# MDBU004A_DRV888x_MSP430F2617.net
KiCad netlist of a schematic drawn in Altium Designer
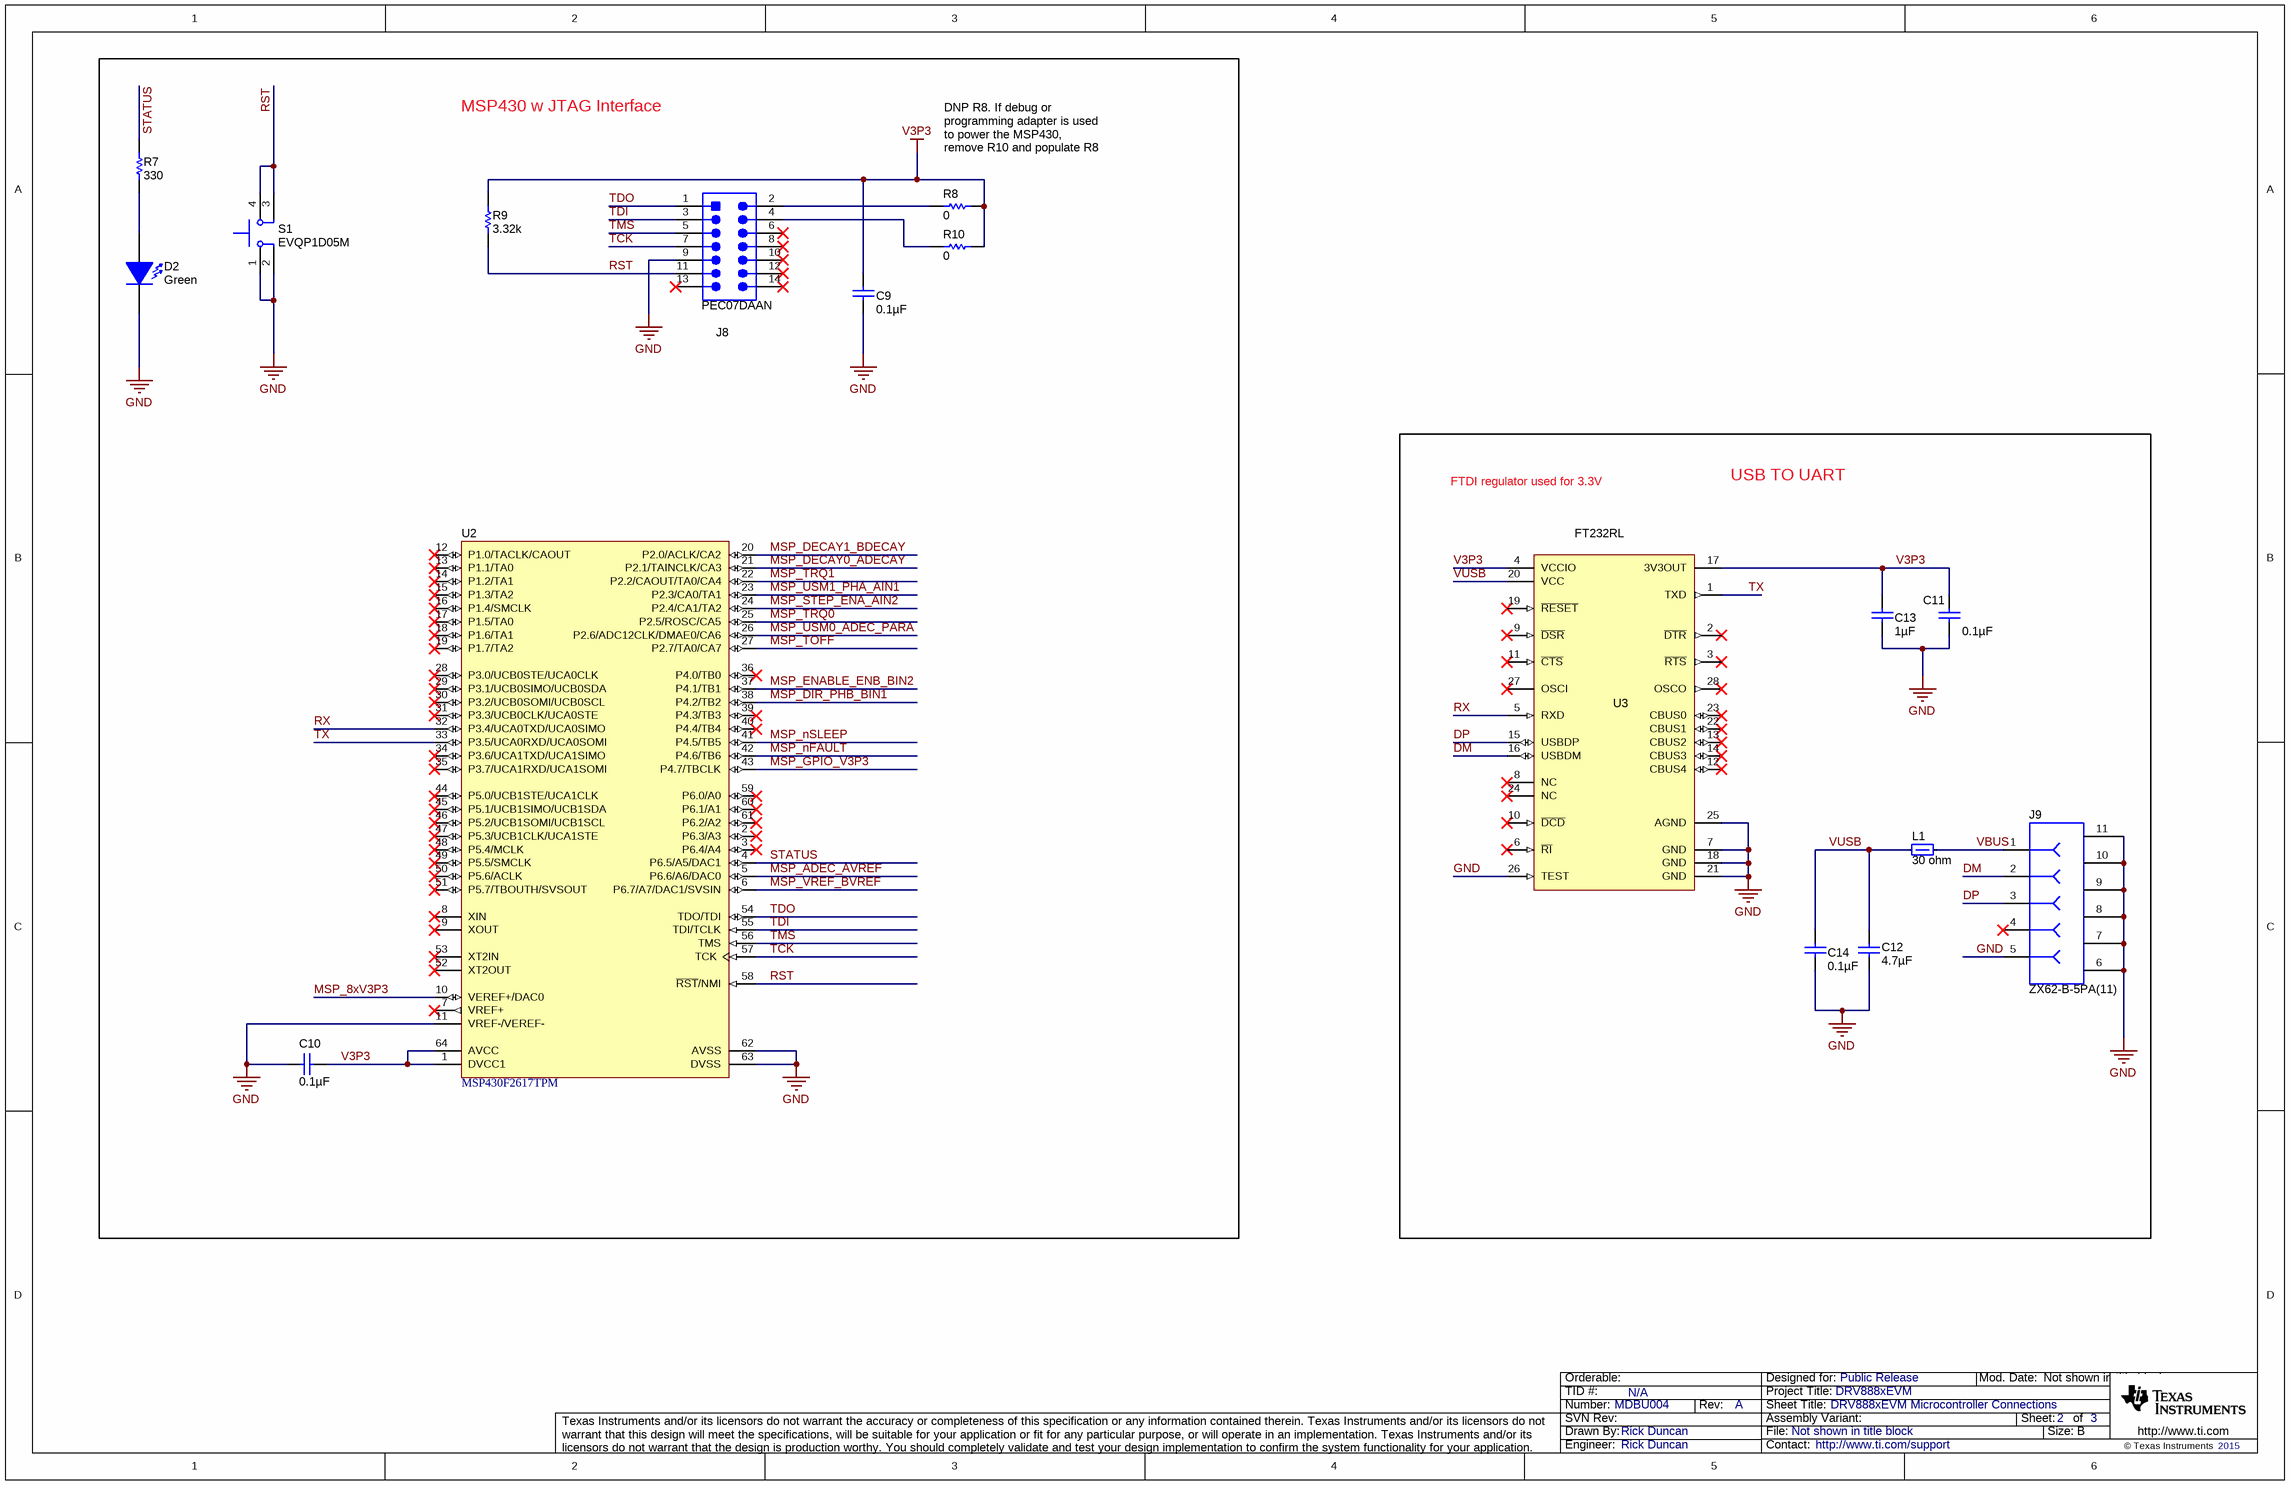
[diagram p0: MDBU004A_DRV888x_MSP430F2617.SchDoc]

(export (version "E")
  (design (tool "Eeschema 10.0.6"))
  (components
    (comp (ref "C9")
      (value "GRM155R61A104KA01D")
      (footprint "0402L")
      (description "CAP, CERM, 0.1 µF, 10 V, +/- 10%, X5R, 0402")
      (fields
        (field (name "MANUFACTURER") "MuRata")
        (field (name "VALUEDISPLAYED") "0.1µF")
        (field (name "PUBLISHER") "Texas Instruments")
      )
      (libsource (lib "Capacitor_Ceramic") (part "GRM155R61A104KA01D"))
    )
    (comp (ref "C10")
      (value "GRM155R61A104KA01D")
      (footprint "0402L")
      (description "CAP, CERM, 0.1 µF, 10 V, +/- 10%, X5R, 0402")
      (fields
        (field (name "MANUFACTURER") "MuRata")
        (field (name "VALUEDISPLAYED") "0.1µF")
        (field (name "PUBLISHER") "Texas Instruments")
      )
      (libsource (lib "Capacitor_Ceramic") (part "GRM155R61A104KA01D"))
    )
    (comp (ref "C11")
      (value "GRM155R61A104KA01D")
      (footprint "0402L")
      (description "CAP, CERM, 0.1 µF, 10 V, +/- 10%, X5R, 0402")
      (fields
        (field (name "MANUFACTURER") "MuRata")
        (field (name "VALUEDISPLAYED") "0.1µF")
        (field (name "PUBLISHER") "Texas Instruments")
      )
      (libsource (lib "Capacitor_Ceramic") (part "GRM155R61A104KA01D"))
    )
    (comp (ref "C12")
      (value "CGB3B1X5R1A475K055AC")
      (footprint "0603L")
      (description "CAP, CERM, 4.7 µF, 10 V, +/- 10%, X5R, 0603")
      (fields
        (field (name "VALUEDISPLAYED") "4.7µF")
        (field (name "MANUFACTURER") "TDK")
        (field (name "PUBLISHER") "Texas Instruments")
      )
      (libsource (lib "Capacitor_Ceramic") (part "CGB3B1X5R1A475K055AC"))
    )
    (comp (ref "C13")
      (value "GRM155R61A105KE15D")
      (footprint "0402L")
      (description "CAP, CERM, 1 µF, 10 V, +/- 10%, X5R, 0402")
      (fields
        (field (name "MANUFACTURER") "MuRata")
        (field (name "VALUEDISPLAYED") "1µF")
        (field (name "PUBLISHER") "Texas Instruments")
      )
      (libsource (lib "Capacitor_Ceramic") (part "GRM155R61A105KE15D"))
    )
    (comp (ref "C14")
      (value "GRM155R61A104KA01D")
      (footprint "0402L")
      (description "CAP, CERM, 0.1 µF, 10 V, +/- 10%, X5R, 0402")
      (fields
        (field (name "MANUFACTURER") "MuRata")
        (field (name "VALUEDISPLAYED") "0.1µF")
        (field (name "PUBLISHER") "Texas Instruments")
      )
      (libsource (lib "Capacitor_Ceramic") (part "GRM155R61A104KA01D"))
    )
    (comp (ref "D2")
      (value "Green")
      (footprint "LED_LTST-C190")
      (description "LED, Green, SMD")
      (fields
        (field (name "MANUFACTURER") "Lite-On")
        (field (name "PARTNUMBER") "LTST-C190GKT")
        (field (name "PUBLISHER") "Texas Instruments")
      )
      (libsource (lib "LED") (part "LTST-C190GKT"))
    )
    (comp (ref "J8")
      (value "PEC07DAAN")
      (footprint "CONN_PEC07DAAN")
      (description "Header, 100mil, 7x2, Tin, TH")
      (fields
        (field (name "MANUFACTURER") "Sullins Connector Solutions")
        (field (name "SYMBOLCREATOR") "a0412235")
        (field (name "PUBLISHER") "Texas Instruments")
      )
      (libsource (lib "Connectors_Sullins") (part "PEC07DAAN"))
    )
    (comp (ref "J9")
      (value "ZX62-B-5PA(11)")
      (footprint "CONN_USB_micro_ZX62-B-5PA")
      (description "Connector, Receptacle, Micro-USB Type B, R/A, Bottom Mount SMT")
      (fields
        (field (name "MANUFACTURER") "Hirose Electric Co. Ltd.")
        (field (name "SYMBOLCREATOR") "a0411947")
        (field (name "PUBLISHER") "Texas Instruments")
      )
      (libsource (lib "Connectors_Other") (part "ZX62-B-5PA(11)"))
    )
    (comp (ref "L1")
      (value "30 ohm")
      (footprint "0805L")
      (description "Ferrite Bead, 30 ohm @ 100 MHz, 1.5 A, 0805")
      (fields
        (field (name "MANUFACTURER") "TDK")
        (field (name "PARTNUMBER") "MMZ2012R300A")
        (field (name "PUBLISHER") "Texas Instruments")
      )
      (libsource (lib "FerriteBead") (part "MMZ2012R300A"))
    )
    (comp (ref "R7")
      (value "330")
      (footprint "0402L")
      (description "RES, 330, 5%, 0.063 W, 0402")
      (fields
        (field (name "MANUFACTURER") "Vishay-Dale")
        (field (name "PARTNUMBER") "CRCW0402330RJNED")
        (field (name "PUBLISHER") "Texas Instruments")
      )
      (libsource (lib "Resistor_0402") (part "CRCW0402330RJNED"))
    )
    (comp (ref "R8")
      (value "0")
      (footprint "0402L")
      (description "RES, 0, 5%, 0.063 W, 0402")
      (fields
        (field (name "MANUFACTURER") "Panasonic")
        (field (name "PARTNUMBER") "ERJ-2GE0R00X")
        (field (name "PUBLISHER") "Texas Instruments")
      )
      (libsource (lib "Resistor_0402") (part "ERJ-2GE0R00X"))
    )
    (comp (ref "R9")
      (value "3.32k")
      (footprint "0402L")
      (description "RES, 3.32 k, 1%, 0.063 W, 0402")
      (fields
        (field (name "MANUFACTURER") "Vishay-Dale")
        (field (name "PARTNUMBER") "CRCW04023K32FKED")
        (field (name "PUBLISHER") "Texas Instruments")
      )
      (libsource (lib "Resistor_0402") (part "CRCW04023K32FKED"))
    )
    (comp (ref "R10")
      (value "0")
      (footprint "0402L")
      (description "RES, 0, 5%, 0.063 W, 0402")
      (fields
        (field (name "MANUFACTURER") "Panasonic")
        (field (name "PARTNUMBER") "ERJ-2GE0R00X")
        (field (name "PUBLISHER") "Texas Instruments")
      )
      (libsource (lib "Resistor_0402") (part "ERJ-2GE0R00X"))
    )
    (comp (ref "S1")
      (value "EVQP1D05M")
      (footprint "SW_EVQxxx05M")
      (description "Switch, Tactile, SPST-NO, 0.05A, 12V, SMT")
      (fields
        (field (name "MANUFACTURER") "Panasonic")
        (field (name "SYMBOLCREATOR") "a0799628")
        (field (name "PUBLISHER") "Texas Instruments")
      )
      (libsource (lib "Switches") (part "EVQP1D05M"))
    )
    (comp (ref "U2")
      (value "MSP430F2617TPM")
      (footprint "PM0064A_L")
      (fields
        (field (name "MANUFACTURER") "Texas Instruments")
        (field (name "ALTERNATE PARTNUMBER") "Equivalent")
      )
      (libsource (lib "TI MCU MSP430") (part "MSP430F2617TPM"))
    )
    (comp (ref "U3")
      (value "FT232RL")
      (footprint "SSOP28_M")
      (description "USB to Serial UART, SSOP28")
      (fields
        (field (name "MANUFACTURER") "FTDI")
        (field (name "SYMBOLCREATOR") "x0208326")
        (field (name "PUBLISHER") "Texas Instruments")
      )
      (libsource (lib "Other_IC") (part "FT232RL"))
    )
  )
  (nets
    (net (code "1") (name "/DM") (class "Default")
      (node (ref "J9") (pin "2") (pinfunction "2_2") (pintype "passive"))
      (node (ref "U3") (pin "16") (pinfunction "USBDM_16") (pintype "bidirectional"))
    )
    (net (code "2") (name "/DP") (class "Default")
      (node (ref "J9") (pin "3") (pinfunction "3_3") (pintype "passive"))
      (node (ref "U3") (pin "15") (pinfunction "USBDP_15") (pintype "bidirectional"))
    )
    (net (code "3") (name "/MSP_8xV3P3") (class "Default")
      (node (ref "U2") (pin "10") (pinfunction "VEREF+/DAC0_10") (pintype "bidirectional"))
    )
    (net (code "4") (name "/MSP_ADEC_AVREF") (class "Default")
      (node (ref "U2") (pin "5") (pinfunction "P6.6/A6/DAC0_5") (pintype "bidirectional"))
    )
    (net (code "5") (name "/MSP_DECAY0_ADECAY") (class "Default")
      (node (ref "U2") (pin "21") (pinfunction "P2.1/TAINCLK/CA3_21") (pintype "bidirectional"))
    )
    (net (code "6") (name "/MSP_DECAY1_BDECAY") (class "Default")
      (node (ref "U2") (pin "20") (pinfunction "P2.0/ACLK/CA2_20") (pintype "bidirectional"))
    )
    (net (code "7") (name "/MSP_DIR_PHB_BIN1") (class "Default")
      (node (ref "U2") (pin "38") (pinfunction "P4.2/TB2_38") (pintype "bidirectional"))
    )
    (net (code "8") (name "/MSP_ENABLE_ENB_BIN2") (class "Default")
      (node (ref "U2") (pin "37") (pinfunction "P4.1/TB1_37") (pintype "bidirectional"))
    )
    (net (code "9") (name "/MSP_GPIO_V3P3") (class "Default")
      (node (ref "U2") (pin "43") (pinfunction "P4.7/TBCLK_43") (pintype "bidirectional"))
    )
    (net (code "10") (name "/MSP_STEP_ENA_AIN2") (class "Default")
      (node (ref "U2") (pin "24") (pinfunction "P2.4/CA1/TA2_24") (pintype "bidirectional"))
    )
    (net (code "11") (name "/MSP_TOFF") (class "Default")
      (node (ref "U2") (pin "27") (pinfunction "P2.7/TA0/CA7_27") (pintype "bidirectional"))
    )
    (net (code "12") (name "/MSP_TRQ0") (class "Default")
      (node (ref "U2") (pin "25") (pinfunction "P2.5/ROSC/CA5_25") (pintype "bidirectional"))
    )
    (net (code "13") (name "/MSP_TRQ1") (class "Default")
      (node (ref "U2") (pin "22") (pinfunction "P2.2/CAOUT/TA0/CA4_22") (pintype "bidirectional"))
    )
    (net (code "14") (name "/MSP_USM0_ADEC_PARA") (class "Default")
      (node (ref "U2") (pin "26") (pinfunction "P2.6/ADC12CLK/DMAE0/CA6_26") (pintype "bidirectional"))
    )
    (net (code "15") (name "/MSP_USM1_PHA_AIN1") (class "Default")
      (node (ref "U2") (pin "23") (pinfunction "P2.3/CA0/TA1_23") (pintype "bidirectional"))
    )
    (net (code "16") (name "/MSP_VREF_BVREF") (class "Default")
      (node (ref "U2") (pin "6") (pinfunction "P6.7/A7/DAC1/SVSIN_6") (pintype "bidirectional"))
    )
    (net (code "17") (name "/MSP_nFAULT") (class "Default")
      (node (ref "U2") (pin "42") (pinfunction "P4.6/TB6_42") (pintype "bidirectional"))
    )
    (net (code "18") (name "/MSP_nSLEEP") (class "Default")
      (node (ref "U2") (pin "41") (pinfunction "P4.5/TB5_41") (pintype "bidirectional"))
    )
    (net (code "19") (name "/RST") (class "Default")
      (node (ref "J8") (pin "11") (pinfunction "11_11") (pintype "passive"))
      (node (ref "R9") (pin "1") (pinfunction "1_1") (pintype "passive"))
      (node (ref "S1") (pin "3") (pinfunction "3_3") (pintype "passive"))
      (node (ref "S1") (pin "4") (pinfunction "4_4") (pintype "passive"))
      (node (ref "U2") (pin "58") (pinfunction "~{RST}/NMI_58") (pintype "input"))
    )
    (net (code "20") (name "/RX") (class "Default")
      (node (ref "U2") (pin "32") (pinfunction "P3.4/UCA0TXD/UCA0SIMO_32") (pintype "bidirectional"))
      (node (ref "U3") (pin "5") (pinfunction "RXD_5") (pintype "input"))
    )
    (net (code "21") (name "/STATUS") (class "Default")
      (node (ref "R7") (pin "2") (pinfunction "2_2") (pintype "passive"))
      (node (ref "U2") (pin "4") (pinfunction "P6.5/A5/DAC1_4") (pintype "bidirectional"))
    )
    (net (code "22") (name "/TCK") (class "Default")
      (node (ref "J8") (pin "7") (pinfunction "7_7") (pintype "passive"))
      (node (ref "U2") (pin "57") (pinfunction "TCK_57") (pintype "input"))
    )
    (net (code "23") (name "/TDI") (class "Default")
      (node (ref "J8") (pin "3") (pinfunction "3_3") (pintype "passive"))
      (node (ref "U2") (pin "55") (pinfunction "TDI/TCLK_55") (pintype "input"))
    )
    (net (code "24") (name "/TDO") (class "Default")
      (node (ref "J8") (pin "1") (pinfunction "1_1") (pintype "passive"))
      (node (ref "U2") (pin "54") (pinfunction "TDO/TDI_54") (pintype "bidirectional"))
    )
    (net (code "25") (name "/TMS") (class "Default")
      (node (ref "J8") (pin "5") (pinfunction "5_5") (pintype "passive"))
      (node (ref "U2") (pin "56") (pinfunction "TMS_56") (pintype "input"))
    )
    (net (code "26") (name "/TX") (class "Default")
      (node (ref "U2") (pin "33") (pinfunction "P3.5/UCA0RXD/UCA0SOMI_33") (pintype "bidirectional"))
      (node (ref "U3") (pin "1") (pinfunction "TXD_1") (pintype "output"))
    )
    (net (code "27") (name "/VBUS") (class "Default")
      (node (ref "J9") (pin "1") (pinfunction "1_1") (pintype "passive"))
      (node (ref "L1") (pin "2") (pinfunction "2_2") (pintype "passive"))
    )
    (net (code "28") (name "/VUSB") (class "Default")
      (node (ref "C12") (pin "1") (pinfunction "1_1") (pintype "passive"))
      (node (ref "C14") (pin "1") (pinfunction "1_1") (pintype "passive"))
      (node (ref "L1") (pin "1") (pinfunction "1_1") (pintype "passive"))
      (node (ref "U3") (pin "20") (pinfunction "VCC_20") (pintype "power_in"))
    )
    (net (code "29") (name "GND") (class "Default")
      (node (ref "C10") (pin "2") (pinfunction "2_2") (pintype "passive"))
      (node (ref "C11") (pin "2") (pinfunction "2_2") (pintype "passive"))
      (node (ref "C12") (pin "2") (pinfunction "2_2") (pintype "passive"))
      (node (ref "C13") (pin "2") (pinfunction "2_2") (pintype "passive"))
      (node (ref "C14") (pin "2") (pinfunction "2_2") (pintype "passive"))
      (node (ref "C9") (pin "2") (pinfunction "2_2") (pintype "passive"))
      (node (ref "D2") (pin "2") (pinfunction "K_2") (pintype "passive"))
      (node (ref "J8") (pin "9") (pinfunction "9_9") (pintype "passive"))
      (node (ref "J9") (pin "10") (pinfunction "10_10") (pintype "passive"))
      (node (ref "J9") (pin "11") (pinfunction "11_11") (pintype "passive"))
      (node (ref "J9") (pin "5") (pinfunction "5_5") (pintype "passive"))
      (node (ref "J9") (pin "6") (pinfunction "6_6") (pintype "passive"))
      (node (ref "J9") (pin "7") (pinfunction "7_7") (pintype "passive"))
      (node (ref "J9") (pin "8") (pinfunction "8_8") (pintype "passive"))
      (node (ref "J9") (pin "9") (pinfunction "9_9") (pintype "passive"))
      (node (ref "S1") (pin "1") (pinfunction "1_1") (pintype "passive"))
      (node (ref "S1") (pin "2") (pinfunction "2_2") (pintype "passive"))
      (node (ref "U2") (pin "11") (pinfunction "VREF-/VEREF-_11") (pintype "passive"))
      (node (ref "U2") (pin "62") (pinfunction "AVSS_62") (pintype "power_in"))
      (node (ref "U2") (pin "63") (pinfunction "DVSS_63") (pintype "power_in"))
      (node (ref "U3") (pin "18") (pinfunction "GND_18") (pintype "power_in"))
      (node (ref "U3") (pin "21") (pinfunction "GND_21") (pintype "power_in"))
      (node (ref "U3") (pin "25") (pinfunction "AGND_25") (pintype "power_in"))
      (node (ref "U3") (pin "26") (pinfunction "TEST_26") (pintype "input"))
      (node (ref "U3") (pin "7") (pinfunction "GND_7") (pintype "power_in"))
    )
    (net (code "30") (name "Net-(D2-A)") (class "Default")
      (node (ref "D2") (pin "1") (pinfunction "A_1") (pintype "passive"))
      (node (ref "R7") (pin "1") (pinfunction "1_1") (pintype "passive"))
    )
    (net (code "31") (name "Net-(J8-Pad2)") (class "Default")
      (node (ref "J8") (pin "2") (pinfunction "2_2") (pintype "passive"))
      (node (ref "R8") (pin "2") (pinfunction "2_2") (pintype "passive"))
    )
    (net (code "32") (name "Net-(J8-Pad4)") (class "Default")
      (node (ref "J8") (pin "4") (pinfunction "4_4") (pintype "passive"))
      (node (ref "R10") (pin "2") (pinfunction "2_2") (pintype "passive"))
    )
    (net (code "33") (name "V3P3") (class "Default")
      (node (ref "C10") (pin "1") (pinfunction "1_1") (pintype "passive"))
      (node (ref "C11") (pin "1") (pinfunction "1_1") (pintype "passive"))
      (node (ref "C13") (pin "1") (pinfunction "1_1") (pintype "passive"))
      (node (ref "C9") (pin "1") (pinfunction "1_1") (pintype "passive"))
      (node (ref "R10") (pin "1") (pinfunction "1_1") (pintype "passive"))
      (node (ref "R8") (pin "1") (pinfunction "1_1") (pintype "passive"))
      (node (ref "R9") (pin "2") (pinfunction "2_2") (pintype "passive"))
      (node (ref "U2") (pin "1") (pinfunction "DVCC1_1") (pintype "power_in"))
      (node (ref "U2") (pin "64") (pinfunction "AVCC_64") (pintype "power_in"))
      (node (ref "U3") (pin "17") (pinfunction "3V3OUT_17") (pintype "power_in"))
      (node (ref "U3") (pin "4") (pinfunction "VCCIO_4") (pintype "power_in"))
    )
    (net (code "34") (name "unconnected-(J8-Pad6)") (class "Default")
      (node (ref "J8") (pin "6") (pinfunction "6_6") (pintype "passive+no_connect"))
    )
    (net (code "35") (name "unconnected-(J8-Pad8)") (class "Default")
      (node (ref "J8") (pin "8") (pinfunction "8_8") (pintype "passive+no_connect"))
    )
    (net (code "36") (name "unconnected-(J8-Pad10)") (class "Default")
      (node (ref "J8") (pin "10") (pinfunction "10_10") (pintype "passive+no_connect"))
    )
    (net (code "37") (name "unconnected-(J8-Pad12)") (class "Default")
      (node (ref "J8") (pin "12") (pinfunction "12_12") (pintype "passive+no_connect"))
    )
    (net (code "38") (name "unconnected-(J8-Pad13)") (class "Default")
      (node (ref "J8") (pin "13") (pinfunction "13_13") (pintype "passive+no_connect"))
    )
    (net (code "39") (name "unconnected-(J8-Pad14)") (class "Default")
      (node (ref "J8") (pin "14") (pinfunction "14_14") (pintype "passive+no_connect"))
    )
    (net (code "40") (name "unconnected-(J9-Pad4)") (class "Default")
      (node (ref "J9") (pin "4") (pinfunction "4_4") (pintype "passive+no_connect"))
    )
    (net (code "41") (name "unconnected-(U2-P1.0{slash}TACLK{slash}CAOUT-Pad12)") (class "Default")
      (node (ref "U2") (pin "12") (pinfunction "P1.0/TACLK/CAOUT_12") (pintype "bidirectional+no_connect"))
    )
    (net (code "42") (name "unconnected-(U2-P1.1{slash}TA0-Pad13)") (class "Default")
      (node (ref "U2") (pin "13") (pinfunction "P1.1/TA0_13") (pintype "bidirectional+no_connect"))
    )
    (net (code "43") (name "unconnected-(U2-P1.2{slash}TA1-Pad14)") (class "Default")
      (node (ref "U2") (pin "14") (pinfunction "P1.2/TA1_14") (pintype "bidirectional+no_connect"))
    )
    (net (code "44") (name "unconnected-(U2-P1.3{slash}TA2-Pad15)") (class "Default")
      (node (ref "U2") (pin "15") (pinfunction "P1.3/TA2_15") (pintype "bidirectional+no_connect"))
    )
    (net (code "45") (name "unconnected-(U2-P1.4{slash}SMCLK-Pad16)") (class "Default")
      (node (ref "U2") (pin "16") (pinfunction "P1.4/SMCLK_16") (pintype "bidirectional+no_connect"))
    )
    (net (code "46") (name "unconnected-(U2-P1.5{slash}TA0-Pad17)") (class "Default")
      (node (ref "U2") (pin "17") (pinfunction "P1.5/TA0_17") (pintype "bidirectional+no_connect"))
    )
    (net (code "47") (name "unconnected-(U2-P1.6{slash}TA1-Pad18)") (class "Default")
      (node (ref "U2") (pin "18") (pinfunction "P1.6/TA1_18") (pintype "bidirectional+no_connect"))
    )
    (net (code "48") (name "unconnected-(U2-P1.7{slash}TA2-Pad19)") (class "Default")
      (node (ref "U2") (pin "19") (pinfunction "P1.7/TA2_19") (pintype "bidirectional+no_connect"))
    )
    (net (code "49") (name "unconnected-(U2-P3.0{slash}UCB0STE{slash}UCA0CLK-Pad28)") (class "Default")
      (node (ref "U2") (pin "28") (pinfunction "P3.0/UCB0STE/UCA0CLK_28") (pintype "bidirectional+no_connect"))
    )
    (net (code "50") (name "unconnected-(U2-P3.1{slash}UCB0SIMO{slash}UCB0SDA-Pad29)") (class "Default")
      (node (ref "U2") (pin "29") (pinfunction "P3.1/UCB0SIMO/UCB0SDA_29") (pintype "bidirectional+no_connect"))
    )
    (net (code "51") (name "unconnected-(U2-P3.2{slash}UCB0SOMI{slash}UCB0SCL-Pad30)") (class "Default")
      (node (ref "U2") (pin "30") (pinfunction "P3.2/UCB0SOMI/UCB0SCL_30") (pintype "bidirectional+no_connect"))
    )
    (net (code "52") (name "unconnected-(U2-P3.3{slash}UCB0CLK{slash}UCA0STE-Pad31)") (class "Default")
      (node (ref "U2") (pin "31") (pinfunction "P3.3/UCB0CLK/UCA0STE_31") (pintype "bidirectional+no_connect"))
    )
    (net (code "53") (name "unconnected-(U2-P3.6{slash}UCA1TXD{slash}UCA1SIMO-Pad34)") (class "Default")
      (node (ref "U2") (pin "34") (pinfunction "P3.6/UCA1TXD/UCA1SIMO_34") (pintype "bidirectional+no_connect"))
    )
    (net (code "54") (name "unconnected-(U2-P3.7{slash}UCA1RXD{slash}UCA1SOMI-Pad35)") (class "Default")
      (node (ref "U2") (pin "35") (pinfunction "P3.7/UCA1RXD/UCA1SOMI_35") (pintype "bidirectional+no_connect"))
    )
    (net (code "55") (name "unconnected-(U2-P4.0{slash}TB0-Pad36)") (class "Default")
      (node (ref "U2") (pin "36") (pinfunction "P4.0/TB0_36") (pintype "bidirectional+no_connect"))
    )
    (net (code "56") (name "unconnected-(U2-P4.3{slash}TB3-Pad39)") (class "Default")
      (node (ref "U2") (pin "39") (pinfunction "P4.3/TB3_39") (pintype "bidirectional+no_connect"))
    )
    (net (code "57") (name "unconnected-(U2-P4.4{slash}TB4-Pad40)") (class "Default")
      (node (ref "U2") (pin "40") (pinfunction "P4.4/TB4_40") (pintype "bidirectional+no_connect"))
    )
    (net (code "58") (name "unconnected-(U2-P5.0{slash}UCB1STE{slash}UCA1CLK-Pad44)") (class "Default")
      (node (ref "U2") (pin "44") (pinfunction "P5.0/UCB1STE/UCA1CLK_44") (pintype "bidirectional+no_connect"))
    )
    (net (code "59") (name "unconnected-(U2-P5.1{slash}UCB1SIMO{slash}UCB1SDA-Pad45)") (class "Default")
      (node (ref "U2") (pin "45") (pinfunction "P5.1/UCB1SIMO/UCB1SDA_45") (pintype "bidirectional+no_connect"))
    )
    (net (code "60") (name "unconnected-(U2-P5.2{slash}UCB1SOMI{slash}UCB1SCL-Pad46)") (class "Default")
      (node (ref "U2") (pin "46") (pinfunction "P5.2/UCB1SOMI/UCB1SCL_46") (pintype "bidirectional+no_connect"))
    )
    (net (code "61") (name "unconnected-(U2-P5.3{slash}UCB1CLK{slash}UCA1STE-Pad47)") (class "Default")
      (node (ref "U2") (pin "47") (pinfunction "P5.3/UCB1CLK/UCA1STE_47") (pintype "bidirectional+no_connect"))
    )
    (net (code "62") (name "unconnected-(U2-P5.4{slash}MCLK-Pad48)") (class "Default")
      (node (ref "U2") (pin "48") (pinfunction "P5.4/MCLK_48") (pintype "bidirectional+no_connect"))
    )
    (net (code "63") (name "unconnected-(U2-P5.5{slash}SMCLK-Pad49)") (class "Default")
      (node (ref "U2") (pin "49") (pinfunction "P5.5/SMCLK_49") (pintype "bidirectional+no_connect"))
    )
    (net (code "64") (name "unconnected-(U2-P5.6{slash}ACLK-Pad50)") (class "Default")
      (node (ref "U2") (pin "50") (pinfunction "P5.6/ACLK_50") (pintype "bidirectional+no_connect"))
    )
    (net (code "65") (name "unconnected-(U2-P5.7{slash}TBOUTH{slash}SVSOUT-Pad51)") (class "Default")
      (node (ref "U2") (pin "51") (pinfunction "P5.7/TBOUTH/SVSOUT_51") (pintype "bidirectional+no_connect"))
    )
    (net (code "66") (name "unconnected-(U2-P6.0{slash}A0-Pad59)") (class "Default")
      (node (ref "U2") (pin "59") (pinfunction "P6.0/A0_59") (pintype "bidirectional+no_connect"))
    )
    (net (code "67") (name "unconnected-(U2-P6.1{slash}A1-Pad60)") (class "Default")
      (node (ref "U2") (pin "60") (pinfunction "P6.1/A1_60") (pintype "bidirectional+no_connect"))
    )
    (net (code "68") (name "unconnected-(U2-P6.2{slash}A2-Pad61)") (class "Default")
      (node (ref "U2") (pin "61") (pinfunction "P6.2/A2_61") (pintype "bidirectional+no_connect"))
    )
    (net (code "69") (name "unconnected-(U2-P6.3{slash}A3-Pad2)") (class "Default")
      (node (ref "U2") (pin "2") (pinfunction "P6.3/A3_2") (pintype "bidirectional+no_connect"))
    )
    (net (code "70") (name "unconnected-(U2-P6.4{slash}A4-Pad3)") (class "Default")
      (node (ref "U2") (pin "3") (pinfunction "P6.4/A4_3") (pintype "bidirectional+no_connect"))
    )
    (net (code "71") (name "unconnected-(U2-VREF+-Pad7)") (class "Default")
      (node (ref "U2") (pin "7") (pinfunction "VREF+_7") (pintype "output+no_connect"))
    )
    (net (code "72") (name "unconnected-(U2-XIN-Pad8)") (class "Default")
      (node (ref "U2") (pin "8") (pinfunction "XIN_8") (pintype "passive+no_connect"))
    )
    (net (code "73") (name "unconnected-(U2-XOUT-Pad9)") (class "Default")
      (node (ref "U2") (pin "9") (pinfunction "XOUT_9") (pintype "passive+no_connect"))
    )
    (net (code "74") (name "unconnected-(U2-XT2IN-Pad53)") (class "Default")
      (node (ref "U2") (pin "53") (pinfunction "XT2IN_53") (pintype "passive+no_connect"))
    )
    (net (code "75") (name "unconnected-(U2-XT2OUT-Pad52)") (class "Default")
      (node (ref "U2") (pin "52") (pinfunction "XT2OUT_52") (pintype "passive+no_connect"))
    )
    (net (code "76") (name "unconnected-(U3-CBUS0-Pad23)") (class "Default")
      (node (ref "U3") (pin "23") (pinfunction "CBUS0_23") (pintype "bidirectional+no_connect"))
    )
    (net (code "77") (name "unconnected-(U3-CBUS1-Pad22)") (class "Default")
      (node (ref "U3") (pin "22") (pinfunction "CBUS1_22") (pintype "bidirectional+no_connect"))
    )
    (net (code "78") (name "unconnected-(U3-CBUS2-Pad13)") (class "Default")
      (node (ref "U3") (pin "13") (pinfunction "CBUS2_13") (pintype "bidirectional+no_connect"))
    )
    (net (code "79") (name "unconnected-(U3-CBUS3-Pad14)") (class "Default")
      (node (ref "U3") (pin "14") (pinfunction "CBUS3_14") (pintype "bidirectional+no_connect"))
    )
    (net (code "80") (name "unconnected-(U3-CBUS4-Pad12)") (class "Default")
      (node (ref "U3") (pin "12") (pinfunction "CBUS4_12") (pintype "bidirectional+no_connect"))
    )
    (net (code "81") (name "unconnected-(U3-CTS-Pad11)") (class "Default")
      (node (ref "U3") (pin "11") (pinfunction "CTS_11") (pintype "input+no_connect"))
    )
    (net (code "82") (name "unconnected-(U3-DCD-Pad10)") (class "Default")
      (node (ref "U3") (pin "10") (pinfunction "DCD_10") (pintype "input+no_connect"))
    )
    (net (code "83") (name "unconnected-(U3-DSR-Pad9)") (class "Default")
      (node (ref "U3") (pin "9") (pinfunction "DSR_9") (pintype "input+no_connect"))
    )
    (net (code "84") (name "unconnected-(U3-DTR-Pad2)") (class "Default")
      (node (ref "U3") (pin "2") (pinfunction "DTR_2") (pintype "output+no_connect"))
    )
    (net (code "85") (name "unconnected-(U3-NC-Pad8)") (class "Default")
      (node (ref "U3") (pin "8") (pinfunction "NC_8") (pintype "passive+no_connect"))
    )
    (net (code "86") (name "unconnected-(U3-NC-Pad24)") (class "Default")
      (node (ref "U3") (pin "24") (pinfunction "NC_24") (pintype "passive+no_connect"))
    )
    (net (code "87") (name "unconnected-(U3-OSCI-Pad27)") (class "Default")
      (node (ref "U3") (pin "27") (pinfunction "OSCI_27") (pintype "passive+no_connect"))
    )
    (net (code "88") (name "unconnected-(U3-OSCO-Pad28)") (class "Default")
      (node (ref "U3") (pin "28") (pinfunction "OSCO_28") (pintype "output+no_connect"))
    )
    (net (code "89") (name "unconnected-(U3-RESET-Pad19)") (class "Default")
      (node (ref "U3") (pin "19") (pinfunction "RESET_19") (pintype "input+no_connect"))
    )
    (net (code "90") (name "unconnected-(U3-RI-Pad6)") (class "Default")
      (node (ref "U3") (pin "6") (pinfunction "RI_6") (pintype "input+no_connect"))
    )
    (net (code "91") (name "unconnected-(U3-RTS-Pad3)") (class "Default")
      (node (ref "U3") (pin "3") (pinfunction "RTS_3") (pintype "output+no_connect"))
    )
  )
)
